# Power.net
KiCad netlist of a schematic drawn in Altium Designer
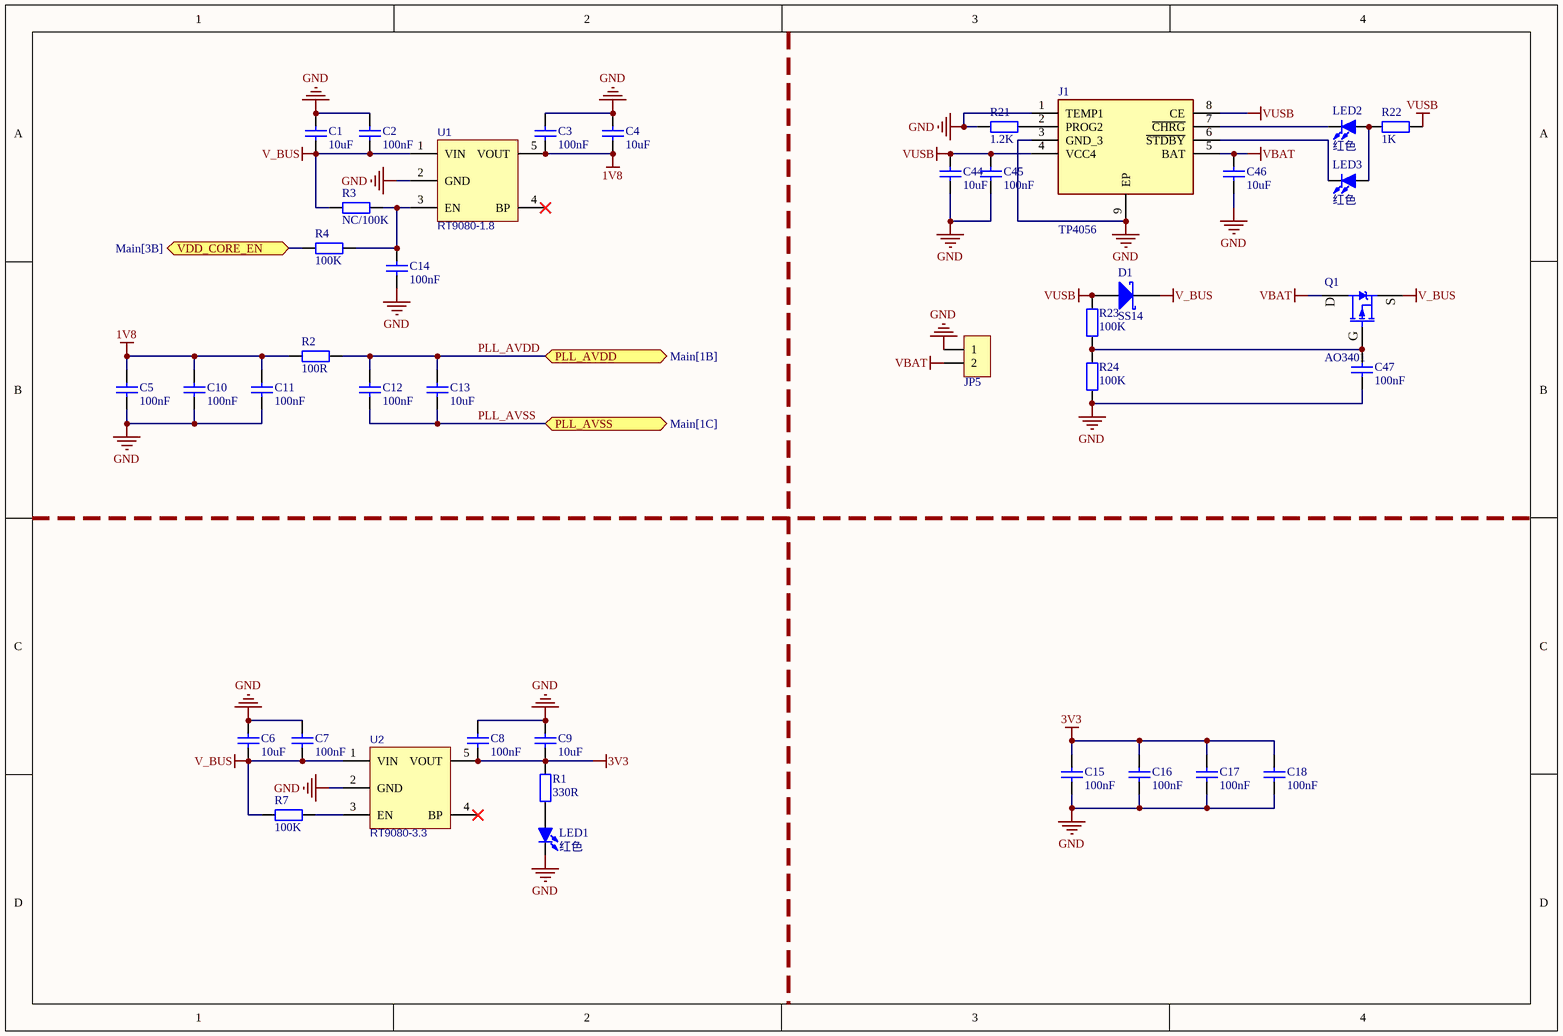
[diagram p0: Power.SchDoc]

(export (version "E")
  (design (tool "Eeschema 10.0.6"))
  (components
    (comp (ref "C1")
      (value "10uF")
      (footprint "C0603_NS")
      (description "贴片电容/MLCC电容")
      (libsource (lib "0.1 - 电阻-电容-电感-晶振-晶体-磁珠-电位器-法拉电容-馈通电容") (part "C"))
    )
    (comp (ref "C2")
      (value "100nF")
      (footprint "C0603_NS")
      (description "贴片电容/MLCC电容")
      (libsource (lib "0.1 - 电阻-电容-电感-晶振-晶体-磁珠-电位器-法拉电容-馈通电容") (part "C"))
    )
    (comp (ref "C3")
      (value "100nF")
      (footprint "C0603_NS")
      (description "贴片电容/MLCC电容")
      (libsource (lib "0.1 - 电阻-电容-电感-晶振-晶体-磁珠-电位器-法拉电容-馈通电容") (part "C"))
    )
    (comp (ref "C4")
      (value "10uF")
      (footprint "C0603_NS")
      (description "贴片电容/MLCC电容")
      (libsource (lib "0.1 - 电阻-电容-电感-晶振-晶体-磁珠-电位器-法拉电容-馈通电容") (part "C"))
    )
    (comp (ref "C5")
      (value "100nF")
      (footprint "C0603_NS")
      (description "贴片电容/MLCC电容")
      (libsource (lib "0.1 - 电阻-电容-电感-晶振-晶体-磁珠-电位器-法拉电容-馈通电容") (part "C"))
    )
    (comp (ref "C6")
      (value "10uF")
      (footprint "C0603_NS")
      (description "贴片电容/MLCC电容")
      (libsource (lib "0.1 - 电阻-电容-电感-晶振-晶体-磁珠-电位器-法拉电容-馈通电容") (part "C"))
    )
    (comp (ref "C7")
      (value "100nF")
      (footprint "C0603_NS")
      (description "贴片电容/MLCC电容")
      (libsource (lib "0.1 - 电阻-电容-电感-晶振-晶体-磁珠-电位器-法拉电容-馈通电容") (part "C"))
    )
    (comp (ref "C8")
      (value "100nF")
      (footprint "C0603_NS")
      (description "贴片电容/MLCC电容")
      (libsource (lib "0.1 - 电阻-电容-电感-晶振-晶体-磁珠-电位器-法拉电容-馈通电容") (part "C"))
    )
    (comp (ref "C9")
      (value "10uF")
      (footprint "C0603_NS")
      (description "贴片电容/MLCC电容")
      (libsource (lib "0.1 - 电阻-电容-电感-晶振-晶体-磁珠-电位器-法拉电容-馈通电容") (part "C"))
    )
    (comp (ref "C10")
      (value "100nF")
      (footprint "C0603_NS")
      (description "贴片电容/MLCC电容")
      (libsource (lib "0.1 - 电阻-电容-电感-晶振-晶体-磁珠-电位器-法拉电容-馈通电容") (part "C"))
    )
    (comp (ref "C11")
      (value "100nF")
      (footprint "C0603_NS")
      (description "贴片电容/MLCC电容")
      (libsource (lib "0.1 - 电阻-电容-电感-晶振-晶体-磁珠-电位器-法拉电容-馈通电容") (part "C"))
    )
    (comp (ref "C12")
      (value "100nF")
      (footprint "C0603_NS")
      (description "贴片电容/MLCC电容")
      (libsource (lib "0.1 - 电阻-电容-电感-晶振-晶体-磁珠-电位器-法拉电容-馈通电容") (part "C"))
    )
    (comp (ref "C13")
      (value "10uF")
      (footprint "C0603_NS")
      (description "贴片电容/MLCC电容")
      (libsource (lib "0.1 - 电阻-电容-电感-晶振-晶体-磁珠-电位器-法拉电容-馈通电容") (part "C"))
    )
    (comp (ref "C14")
      (value "100nF")
      (footprint "C0603_NS")
      (description "贴片电容/MLCC电容")
      (libsource (lib "0.1 - 电阻-电容-电感-晶振-晶体-磁珠-电位器-法拉电容-馈通电容") (part "C"))
    )
    (comp (ref "C15")
      (value "100nF")
      (footprint "C0603_NS")
      (description "贴片电容/MLCC电容")
      (libsource (lib "0.1 - 电阻-电容-电感-晶振-晶体-磁珠-电位器-法拉电容-馈通电容") (part "C"))
    )
    (comp (ref "C16")
      (value "100nF")
      (footprint "C0603_NS")
      (description "贴片电容/MLCC电容")
      (libsource (lib "0.1 - 电阻-电容-电感-晶振-晶体-磁珠-电位器-法拉电容-馈通电容") (part "C"))
    )
    (comp (ref "C17")
      (value "100nF")
      (footprint "C0603_NS")
      (description "贴片电容/MLCC电容")
      (libsource (lib "0.1 - 电阻-电容-电感-晶振-晶体-磁珠-电位器-法拉电容-馈通电容") (part "C"))
    )
    (comp (ref "C18")
      (value "100nF")
      (footprint "C0603_NS")
      (description "贴片电容/MLCC电容")
      (libsource (lib "0.1 - 电阻-电容-电感-晶振-晶体-磁珠-电位器-法拉电容-馈通电容") (part "C"))
    )
    (comp (ref "C44")
      (value "10uF")
      (footprint "C0603_NS")
      (description "贴片电容/MLCC电容")
      (libsource (lib "0.1 - 电阻-电容-电感-晶振-晶体-磁珠-电位器-法拉电容-馈通电容") (part "C"))
    )
    (comp (ref "C45")
      (value "100nF")
      (footprint "C0603_NS")
      (description "贴片电容/MLCC电容")
      (libsource (lib "0.1 - 电阻-电容-电感-晶振-晶体-磁珠-电位器-法拉电容-馈通电容") (part "C"))
    )
    (comp (ref "C46")
      (value "10uF")
      (footprint "C0603_NS")
      (description "贴片电容/MLCC电容")
      (libsource (lib "0.1 - 电阻-电容-电感-晶振-晶体-磁珠-电位器-法拉电容-馈通电容") (part "C"))
    )
    (comp (ref "C47")
      (value "100nF")
      (footprint "C0603_NS")
      (description "贴片电容/MLCC电容")
      (libsource (lib "0.1 - 电阻-电容-电感-晶振-晶体-磁珠-电位器-法拉电容-馈通电容") (part "C"))
    )
    (comp (ref "D1")
      (value "SS14")
      (footprint "SMA")
      (description "肖特基二极管")
      (libsource (lib "0.2 - 二极管-TVS-ESD-整流桥-放电管") (part "SS14"))
    )
    (comp (ref "J1")
      (value "TP4056")
      (footprint "SOIC127P600X175-9N")
      (description "Connector")
      (libsource (lib "*") (part "TP4056"))
    )
    (comp (ref "JP5")
      (value "HDR-1X2")
      (footprint "XH2.54-LS-2P")
      (description "2P接插件")
      (libsource (lib "5.5 - 2.54mm连接器(KF2EDGK_XH2.54_2.54排针排母)") (part "Header 2"))
    )
    (comp (ref "LED1")
      (value "红色")
      (footprint "LED0603_R")
      (description "贴片LED")
      (libsource (lib "0.3 - LED发光二极管-IR二极管_接收管-光耦") (part "LED-SMD"))
    )
    (comp (ref "LED2")
      (value "红色")
      (footprint "LED0603_R")
      (description "贴片LED")
      (libsource (lib "0.3 - LED发光二极管-IR二极管_接收管-光耦") (part "LED-SMD"))
    )
    (comp (ref "LED3")
      (value "红色")
      (footprint "LED0603_R")
      (description "贴片LED")
      (libsource (lib "0.3 - LED发光二极管-IR二极管_接收管-光耦") (part "LED-SMD"))
    )
    (comp (ref "Q1")
      (value "AO3401")
      (footprint "SOT23-3N")
      (description "P沟道 30V/4.2A")
      (libsource (lib "0.4 - 三极管-场效应管-可控硅") (part "AO3401"))
    )
    (comp (ref "R1")
      (value "330R")
      (footprint "R0603_NS")
      (description "贴片电阻")
      (libsource (lib "0.1 - 电阻-电容-电感-晶振-晶体-磁珠-电位器-法拉电容-馈通电容") (part "R"))
    )
    (comp (ref "R2")
      (value "100R")
      (footprint "R0603_NS")
      (description "贴片电阻")
      (libsource (lib "0.1 - 电阻-电容-电感-晶振-晶体-磁珠-电位器-法拉电容-馈通电容") (part "R"))
    )
    (comp (ref "R3")
      (value "NC/100K")
      (footprint "R0603_NS")
      (description "贴片电阻")
      (libsource (lib "0.1 - 电阻-电容-电感-晶振-晶体-磁珠-电位器-法拉电容-馈通电容") (part "R"))
    )
    (comp (ref "R4")
      (value "100K")
      (footprint "R0603_NS")
      (description "贴片电阻")
      (libsource (lib "0.1 - 电阻-电容-电感-晶振-晶体-磁珠-电位器-法拉电容-馈通电容") (part "R"))
    )
    (comp (ref "R7")
      (value "100K")
      (footprint "R0603_NS")
      (description "贴片电阻")
      (libsource (lib "0.1 - 电阻-电容-电感-晶振-晶体-磁珠-电位器-法拉电容-馈通电容") (part "R"))
    )
    (comp (ref "R21")
      (value "1.2K")
      (footprint "R0603_NS")
      (description "贴片电阻")
      (libsource (lib "0.1 - 电阻-电容-电感-晶振-晶体-磁珠-电位器-法拉电容-馈通电容") (part "R"))
    )
    (comp (ref "R22")
      (value "1K")
      (footprint "R0603_NS")
      (description "贴片电阻")
      (libsource (lib "0.1 - 电阻-电容-电感-晶振-晶体-磁珠-电位器-法拉电容-馈通电容") (part "R"))
    )
    (comp (ref "R23")
      (value "100K")
      (footprint "R0603_NS")
      (description "贴片电阻")
      (libsource (lib "0.1 - 电阻-电容-电感-晶振-晶体-磁珠-电位器-法拉电容-馈通电容") (part "R"))
    )
    (comp (ref "R24")
      (value "100K")
      (footprint "R0603_NS")
      (description "贴片电阻")
      (libsource (lib "0.1 - 电阻-电容-电感-晶振-晶体-磁珠-电位器-法拉电容-馈通电容") (part "R"))
    )
    (comp (ref "U1")
      (value "RT9080-1.8")
      (footprint "SOT-23-5")
      (description "LDO 1.8V/0.3A")
      (libsource (lib "0.7 - 电源类芯片") (part "RT9193-18GB"))
    )
    (comp (ref "U2")
      (value "RT9080-3.3")
      (footprint "SOT-23-5")
      (description "LDO 1.8V/0.3A")
      (libsource (lib "0.7 - 电源类芯片") (part "RT9193-18GB"))
    )
  )
  (nets
    (net (code "1") (name "/PLL_AVDD") (class "Default")
      (node (ref "C12") (pin "2") (pinfunction "2_2") (pintype "passive"))
      (node (ref "C13") (pin "2") (pinfunction "2_2") (pintype "passive"))
      (node (ref "R2") (pin "2") (pinfunction "2_2") (pintype "passive"))
    )
    (net (code "2") (name "/PLL_AVSS") (class "Default")
      (node (ref "C12") (pin "1") (pinfunction "1_1") (pintype "passive"))
      (node (ref "C13") (pin "1") (pinfunction "1_1") (pintype "passive"))
    )
    (net (code "3") (name "/VDD_CORE_EN") (class "Default")
      (node (ref "R4") (pin "1") (pinfunction "1_1") (pintype "passive"))
    )
    (net (code "4") (name "1V8") (class "Default")
      (node (ref "C10") (pin "1") (pinfunction "1_1") (pintype "passive"))
      (node (ref "C11") (pin "2") (pinfunction "2_2") (pintype "passive"))
      (node (ref "C3") (pin "1") (pinfunction "1_1") (pintype "passive"))
      (node (ref "C4") (pin "1") (pinfunction "1_1") (pintype "passive"))
      (node (ref "C5") (pin "2") (pinfunction "2_2") (pintype "passive"))
      (node (ref "R2") (pin "1") (pinfunction "1_1") (pintype "passive"))
      (node (ref "U1") (pin "5") (pinfunction "VOUT_5") (pintype "passive"))
    )
    (net (code "5") (name "3V3") (class "Default")
      (node (ref "C15") (pin "2") (pinfunction "2_2") (pintype "passive"))
      (node (ref "C16") (pin "2") (pinfunction "2_2") (pintype "passive"))
      (node (ref "C17") (pin "2") (pinfunction "2_2") (pintype "passive"))
      (node (ref "C18") (pin "2") (pinfunction "2_2") (pintype "passive"))
      (node (ref "C8") (pin "1") (pinfunction "1_1") (pintype "passive"))
      (node (ref "C9") (pin "1") (pinfunction "1_1") (pintype "passive"))
      (node (ref "R1") (pin "1") (pinfunction "1_1") (pintype "passive"))
      (node (ref "U2") (pin "5") (pinfunction "VOUT_5") (pintype "passive"))
    )
    (net (code "6") (name "GND") (class "Default")
      (node (ref "C1") (pin "2") (pinfunction "2_2") (pintype "passive"))
      (node (ref "C10") (pin "2") (pinfunction "2_2") (pintype "passive"))
      (node (ref "C11") (pin "1") (pinfunction "1_1") (pintype "passive"))
      (node (ref "C14") (pin "1") (pinfunction "1_1") (pintype "passive"))
      (node (ref "C15") (pin "1") (pinfunction "1_1") (pintype "passive"))
      (node (ref "C16") (pin "1") (pinfunction "1_1") (pintype "passive"))
      (node (ref "C17") (pin "1") (pinfunction "1_1") (pintype "passive"))
      (node (ref "C18") (pin "1") (pinfunction "1_1") (pintype "passive"))
      (node (ref "C2") (pin "2") (pinfunction "2_2") (pintype "passive"))
      (node (ref "C3") (pin "2") (pinfunction "2_2") (pintype "passive"))
      (node (ref "C4") (pin "2") (pinfunction "2_2") (pintype "passive"))
      (node (ref "C44") (pin "1") (pinfunction "1_1") (pintype "passive"))
      (node (ref "C45") (pin "1") (pinfunction "1_1") (pintype "passive"))
      (node (ref "C46") (pin "1") (pinfunction "1_1") (pintype "passive"))
      (node (ref "C47") (pin "1") (pinfunction "1_1") (pintype "passive"))
      (node (ref "C5") (pin "1") (pinfunction "1_1") (pintype "passive"))
      (node (ref "C6") (pin "2") (pinfunction "2_2") (pintype "passive"))
      (node (ref "C7") (pin "2") (pinfunction "2_2") (pintype "passive"))
      (node (ref "C8") (pin "2") (pinfunction "2_2") (pintype "passive"))
      (node (ref "C9") (pin "2") (pinfunction "2_2") (pintype "passive"))
      (node (ref "J1") (pin "1") (pinfunction "TEMP1_1") (pintype "passive"))
      (node (ref "J1") (pin "3") (pinfunction "GND_3_3") (pintype "passive"))
      (node (ref "J1") (pin "9") (pinfunction "EP_9") (pintype "passive"))
      (node (ref "JP5") (pin "1") (pinfunction "1_1") (pintype "passive"))
      (node (ref "LED1") (pin "2") (pinfunction "K_2") (pintype "passive"))
      (node (ref "R21") (pin "1") (pinfunction "1_1") (pintype "passive"))
      (node (ref "R24") (pin "1") (pinfunction "1_1") (pintype "passive"))
      (node (ref "U1") (pin "2") (pinfunction "GND_2") (pintype "passive"))
      (node (ref "U2") (pin "2") (pinfunction "GND_2") (pintype "passive"))
    )
    (net (code "7") (name "Net-(J1-PROG2)") (class "Default")
      (node (ref "J1") (pin "2") (pinfunction "PROG2_2") (pintype "passive"))
      (node (ref "R21") (pin "2") (pinfunction "2_2") (pintype "passive"))
    )
    (net (code "8") (name "Net-(J1-~{CHRG})") (class "Default")
      (node (ref "J1") (pin "7") (pinfunction "~{CHRG}_7") (pintype "passive"))
      (node (ref "LED2") (pin "2") (pinfunction "K_2") (pintype "passive"))
    )
    (net (code "9") (name "Net-(J1-~{STDBY})") (class "Default")
      (node (ref "J1") (pin "6") (pinfunction "~{STDBY}_6") (pintype "passive"))
      (node (ref "LED3") (pin "2") (pinfunction "K_2") (pintype "passive"))
    )
    (net (code "10") (name "Net-(LED1-A)") (class "Default")
      (node (ref "LED1") (pin "1") (pinfunction "A_1") (pintype "passive"))
      (node (ref "R1") (pin "2") (pinfunction "2_2") (pintype "passive"))
    )
    (net (code "11") (name "Net-(LED2-A)") (class "Default")
      (node (ref "LED2") (pin "1") (pinfunction "A_1") (pintype "passive"))
      (node (ref "LED3") (pin "1") (pinfunction "A_1") (pintype "passive"))
      (node (ref "R22") (pin "1") (pinfunction "1_1") (pintype "passive"))
    )
    (net (code "12") (name "Net-(Q1-G)") (class "Default")
      (node (ref "C47") (pin "2") (pinfunction "2_2") (pintype "passive"))
      (node (ref "Q1") (pin "1") (pinfunction "G_1") (pintype "passive"))
      (node (ref "R23") (pin "1") (pinfunction "1_1") (pintype "passive"))
      (node (ref "R24") (pin "2") (pinfunction "2_2") (pintype "passive"))
    )
    (net (code "13") (name "Net-(U1-EN)") (class "Default")
      (node (ref "C14") (pin "2") (pinfunction "2_2") (pintype "passive"))
      (node (ref "R3") (pin "2") (pinfunction "2_2") (pintype "passive"))
      (node (ref "R4") (pin "2") (pinfunction "2_2") (pintype "passive"))
      (node (ref "U1") (pin "3") (pinfunction "EN_3") (pintype "passive"))
    )
    (net (code "14") (name "Net-(U2-EN)") (class "Default")
      (node (ref "R7") (pin "2") (pinfunction "2_2") (pintype "passive"))
      (node (ref "U2") (pin "3") (pinfunction "EN_3") (pintype "passive"))
    )
    (net (code "15") (name "VBAT") (class "Default")
      (node (ref "C46") (pin "2") (pinfunction "2_2") (pintype "passive"))
      (node (ref "J1") (pin "5") (pinfunction "BAT_5") (pintype "passive"))
      (node (ref "JP5") (pin "2") (pinfunction "2_2") (pintype "passive"))
      (node (ref "Q1") (pin "3") (pinfunction "D_3") (pintype "passive"))
    )
    (net (code "16") (name "VUSB") (class "Default")
      (node (ref "C44") (pin "2") (pinfunction "2_2") (pintype "passive"))
      (node (ref "C45") (pin "2") (pinfunction "2_2") (pintype "passive"))
      (node (ref "D1") (pin "1") (pinfunction "A_1") (pintype "passive"))
      (node (ref "J1") (pin "4") (pinfunction "VCC4_4") (pintype "passive"))
      (node (ref "J1") (pin "8") (pinfunction "CE_8") (pintype "passive"))
      (node (ref "R22") (pin "2") (pinfunction "2_2") (pintype "passive"))
      (node (ref "R23") (pin "2") (pinfunction "2_2") (pintype "passive"))
    )
    (net (code "17") (name "V_BUS") (class "Default")
      (node (ref "C1") (pin "1") (pinfunction "1_1") (pintype "passive"))
      (node (ref "C2") (pin "1") (pinfunction "1_1") (pintype "passive"))
      (node (ref "C6") (pin "1") (pinfunction "1_1") (pintype "passive"))
      (node (ref "C7") (pin "1") (pinfunction "1_1") (pintype "passive"))
      (node (ref "D1") (pin "2") (pinfunction "K_2") (pintype "passive"))
      (node (ref "Q1") (pin "2") (pinfunction "S_2") (pintype "passive"))
      (node (ref "R3") (pin "1") (pinfunction "1_1") (pintype "passive"))
      (node (ref "R7") (pin "1") (pinfunction "1_1") (pintype "passive"))
      (node (ref "U1") (pin "1") (pinfunction "VIN_1") (pintype "passive"))
      (node (ref "U2") (pin "1") (pinfunction "VIN_1") (pintype "passive"))
    )
    (net (code "18") (name "unconnected-(U1-BP-Pad4)") (class "Default")
      (node (ref "U1") (pin "4") (pinfunction "BP_4") (pintype "passive+no_connect"))
    )
    (net (code "19") (name "unconnected-(U2-BP-Pad4)") (class "Default")
      (node (ref "U2") (pin "4") (pinfunction "BP_4") (pintype "passive+no_connect"))
    )
  )
)
